# ArduinoSIDInterface.net
KiCad netlist of a schematic drawn in EAGLE
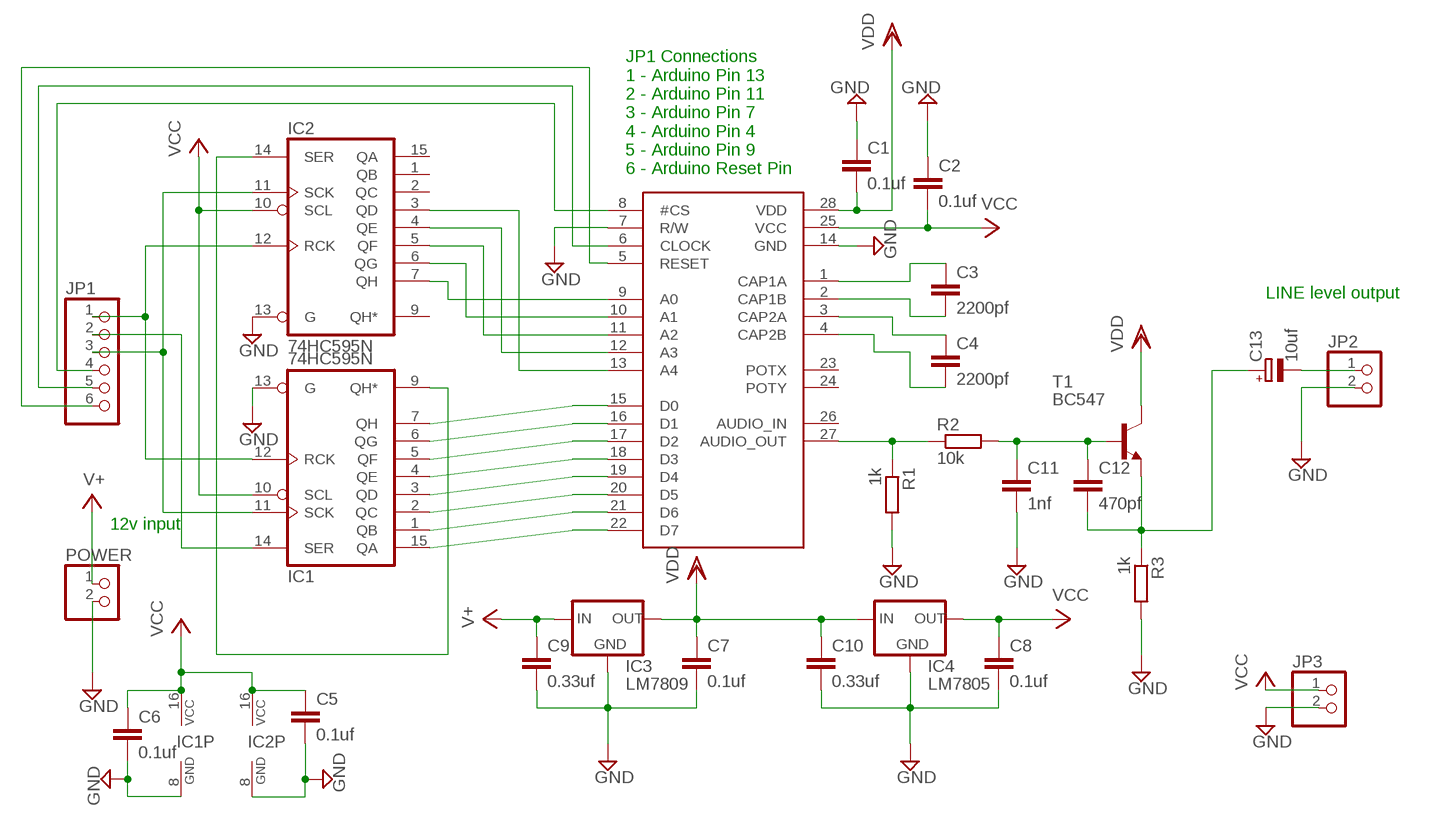
[diagram p0: schematic, sheet 1]

(export (version "E")
  (design (tool "Eeschema 10.0.6"))
  (components
    (comp (ref "C1")
      (value "0.1uf")
      (footprint "eagle-import:C050-035X075")
      (libsource (lib "eagle-import") (part "C-EU050-035X075"))
    )
    (comp (ref "C2")
      (value "0.1uf")
      (footprint "eagle-import:C050-030X075")
      (libsource (lib "eagle-import") (part "C-EU050-030X075"))
    )
    (comp (ref "C3")
      (value "2200pf")
      (footprint "eagle-import:C075-042X103")
      (libsource (lib "eagle-import") (part "C-EU075-042X103"))
    )
    (comp (ref "C4")
      (value "2200pf")
      (footprint "eagle-import:C075-042X103")
      (libsource (lib "eagle-import") (part "C-EU075-042X103"))
    )
    (comp (ref "C5")
      (value "0.1uf")
      (footprint "eagle-import:C050-030X075")
      (libsource (lib "eagle-import") (part "C-EU050-030X075"))
    )
    (comp (ref "C6")
      (value "0.1uf")
      (footprint "eagle-import:C050-030X075")
      (libsource (lib "eagle-import") (part "C-EU050-030X075"))
    )
    (comp (ref "C7")
      (value "0.1uf")
      (footprint "eagle-import:C10B4")
      (libsource (lib "eagle-import") (part "C10/4"))
    )
    (comp (ref "C8")
      (value "0.1uf")
      (footprint "eagle-import:C10B4")
      (libsource (lib "eagle-import") (part "C10/4"))
    )
    (comp (ref "C9")
      (value "0.33uf")
      (footprint "eagle-import:C15B5")
      (libsource (lib "eagle-import") (part "C15/5"))
    )
    (comp (ref "C10")
      (value "0.33uf")
      (footprint "eagle-import:C15B5")
      (libsource (lib "eagle-import") (part "C15/5"))
    )
    (comp (ref "C11")
      (value "1nf")
      (footprint "eagle-import:C050-030X075")
      (libsource (lib "eagle-import") (part "C-EU050-030X075"))
    )
    (comp (ref "C12")
      (value "470pf")
      (footprint "eagle-import:C050-030X075")
      (libsource (lib "eagle-import") (part "C-EU050-030X075"))
    )
    (comp (ref "C13")
      (value "10uf")
      (footprint "eagle-import:E2-5")
      (libsource (lib "eagle-import") (part "CPOL-EUE2-5"))
    )
    (comp (ref "IC1")
      (value "74HC595N")
      (footprint "eagle-import:DIL16")
      (libsource (lib "eagle-import") (part "74595NHC"))
    )
    (comp (ref "IC2")
      (value "74HC595N")
      (footprint "eagle-import:DIL16")
      (libsource (lib "eagle-import") (part "74595NHC"))
    )
    (comp (ref "IC3")
      (value "LM7809")
      (footprint "eagle-import:78XXS")
      (libsource (lib "eagle-import") (part "78XXS"))
    )
    (comp (ref "IC4")
      (value "LM7805")
      (footprint "eagle-import:78XXS")
      (libsource (lib "eagle-import") (part "78XXS"))
    )
    (comp (ref "JP1")
      (value "PINHD-1X6")
      (footprint "eagle-import:1X06")
      (libsource (lib "eagle-import") (part "PINHD-1X6"))
    )
    (comp (ref "JP2")
      (value "PINHD-1X2")
      (footprint "eagle-import:1X02")
      (libsource (lib "eagle-import") (part "PINHD-1X2"))
    )
    (comp (ref "JP3")
      (value "PINHD-1X2")
      (footprint "eagle-import:1X02")
      (libsource (lib "eagle-import") (part "PINHD-1X2"))
    )
    (comp (ref "POWER")
      (value "PINHD-1X2")
      (footprint "eagle-import:1X02")
      (libsource (lib "eagle-import") (part "PINHD-1X2"))
    )
    (comp (ref "R1")
      (value "1k")
      (footprint "eagle-import:0204_7")
      (libsource (lib "eagle-import") (part "R-EU_0204/7"))
    )
    (comp (ref "R2")
      (value "10k")
      (footprint "eagle-import:0204_7")
      (libsource (lib "eagle-import") (part "R-EU_0204/7"))
    )
    (comp (ref "R3")
      (value "1k")
      (footprint "eagle-import:0204_7")
      (libsource (lib "eagle-import") (part "R-EU_0204/7"))
    )
    (comp (ref "T1")
      (value "BC547")
      (footprint "eagle-import:TO92")
      (libsource (lib "eagle-import") (part "BC547"))
    )
    (comp (ref "U$1")
      (value "6581")
      (footprint "eagle-import:DIL28-6")
      (libsource (lib "eagle-import") (part "6581"))
    )
  )
  (nets
    (net (code "1") (name "/D0") (class "Default")
      (node (ref "IC1") (pin "7") (pinfunction "QH_7") (pintype "tri_state"))
      (node (ref "U$1") (pin "15") (pinfunction "D0_15") (pintype "bidirectional"))
    )
    (net (code "2") (name "/D1") (class "Default")
      (node (ref "IC1") (pin "6") (pinfunction "QG_6") (pintype "tri_state"))
      (node (ref "U$1") (pin "16") (pinfunction "D1_16") (pintype "bidirectional"))
    )
    (net (code "3") (name "/D2") (class "Default")
      (node (ref "IC1") (pin "5") (pinfunction "QF_5") (pintype "tri_state"))
      (node (ref "U$1") (pin "17") (pinfunction "D2_17") (pintype "bidirectional"))
    )
    (net (code "4") (name "/D3") (class "Default")
      (node (ref "IC1") (pin "4") (pinfunction "QE_4") (pintype "tri_state"))
      (node (ref "U$1") (pin "18") (pinfunction "D3_18") (pintype "bidirectional"))
    )
    (net (code "5") (name "/D4") (class "Default")
      (node (ref "IC1") (pin "3") (pinfunction "QD_3") (pintype "tri_state"))
      (node (ref "U$1") (pin "19") (pinfunction "D4_19") (pintype "bidirectional"))
    )
    (net (code "6") (name "/D5") (class "Default")
      (node (ref "IC1") (pin "2") (pinfunction "QC_2") (pintype "tri_state"))
      (node (ref "U$1") (pin "20") (pinfunction "D5_20") (pintype "bidirectional"))
    )
    (net (code "7") (name "/D6") (class "Default")
      (node (ref "IC1") (pin "1") (pinfunction "QB_1") (pintype "tri_state"))
      (node (ref "U$1") (pin "21") (pinfunction "D6_21") (pintype "bidirectional"))
    )
    (net (code "8") (name "/D7") (class "Default")
      (node (ref "IC1") (pin "15") (pinfunction "QA_15") (pintype "tri_state"))
      (node (ref "U$1") (pin "22") (pinfunction "D7_22") (pintype "bidirectional"))
    )
    (net (code "9") (name "GND") (class "Default")
      (node (ref "C1") (pin "1") (pinfunction "1_1") (pintype "passive"))
      (node (ref "C10") (pin "2") (pinfunction "2_2") (pintype "passive"))
      (node (ref "C11") (pin "2") (pinfunction "2_2") (pintype "passive"))
      (node (ref "C2") (pin "1") (pinfunction "1_1") (pintype "passive"))
      (node (ref "C5") (pin "2") (pinfunction "2_2") (pintype "passive"))
      (node (ref "C6") (pin "2") (pinfunction "2_2") (pintype "passive"))
      (node (ref "C7") (pin "2") (pinfunction "2_2") (pintype "passive"))
      (node (ref "C8") (pin "2") (pinfunction "2_2") (pintype "passive"))
      (node (ref "C9") (pin "2") (pinfunction "2_2") (pintype "passive"))
      (node (ref "IC1") (pin "13") (pinfunction "G_13") (pintype "input"))
      (node (ref "IC1") (pin "8") (pinfunction "GND_8") (pintype "power_in"))
      (node (ref "IC2") (pin "13") (pinfunction "G_13") (pintype "input"))
      (node (ref "IC2") (pin "8") (pinfunction "GND_8") (pintype "power_in"))
      (node (ref "IC3") (pin "GND") (pinfunction "GND_GND") (pintype "input"))
      (node (ref "IC4") (pin "GND") (pinfunction "GND_GND") (pintype "input"))
      (node (ref "JP2") (pin "2") (pinfunction "2_2") (pintype "passive"))
      (node (ref "JP3") (pin "2") (pinfunction "2_2") (pintype "passive"))
      (node (ref "POWER") (pin "2") (pinfunction "2_2") (pintype "passive"))
      (node (ref "R1") (pin "2") (pinfunction "2_2") (pintype "passive"))
      (node (ref "R3") (pin "2") (pinfunction "2_2") (pintype "passive"))
      (node (ref "U$1") (pin "14") (pinfunction "GND_14") (pintype "bidirectional"))
      (node (ref "U$1") (pin "7") (pinfunction "R/W_7") (pintype "bidirectional"))
    )
    (net (code "10") (name "Net-(C13-Pad-)") (class "Default")
      (node (ref "C13") (pin "-") (pinfunction "-_-") (pintype "passive"))
      (node (ref "JP2") (pin "1") (pinfunction "1_1") (pintype "passive"))
    )
    (net (code "11") (name "Net-(IC1A-QH*)") (class "Default")
      (node (ref "IC1") (pin "9") (pinfunction "QH*_9") (pintype "tri_state"))
      (node (ref "IC2") (pin "14") (pinfunction "SER_14") (pintype "input"))
    )
    (net (code "12") (name "Net-(IC1A-RCK)") (class "Default")
      (node (ref "IC1") (pin "12") (pinfunction "RCK_12") (pintype "input"))
      (node (ref "IC2") (pin "12") (pinfunction "RCK_12") (pintype "input"))
      (node (ref "JP1") (pin "1") (pinfunction "1_1") (pintype "passive"))
    )
    (net (code "13") (name "Net-(IC1A-SCK)") (class "Default")
      (node (ref "IC1") (pin "11") (pinfunction "SCK_11") (pintype "input"))
      (node (ref "IC2") (pin "11") (pinfunction "SCK_11") (pintype "input"))
      (node (ref "JP1") (pin "3") (pinfunction "3_3") (pintype "passive"))
    )
    (net (code "14") (name "Net-(IC1A-SER)") (class "Default")
      (node (ref "IC1") (pin "14") (pinfunction "SER_14") (pintype "input"))
      (node (ref "JP1") (pin "2") (pinfunction "2_2") (pintype "passive"))
    )
    (net (code "15") (name "Net-(IC2A-QD)") (class "Default")
      (node (ref "IC2") (pin "3") (pinfunction "QD_3") (pintype "tri_state"))
      (node (ref "U$1") (pin "13") (pinfunction "A4_13") (pintype "bidirectional"))
    )
    (net (code "16") (name "Net-(IC2A-QE)") (class "Default")
      (node (ref "IC2") (pin "4") (pinfunction "QE_4") (pintype "tri_state"))
      (node (ref "U$1") (pin "12") (pinfunction "A3_12") (pintype "bidirectional"))
    )
    (net (code "17") (name "Net-(IC2A-QF)") (class "Default")
      (node (ref "IC2") (pin "5") (pinfunction "QF_5") (pintype "tri_state"))
      (node (ref "U$1") (pin "11") (pinfunction "A2_11") (pintype "bidirectional"))
    )
    (net (code "18") (name "Net-(IC2A-QG)") (class "Default")
      (node (ref "IC2") (pin "6") (pinfunction "QG_6") (pintype "tri_state"))
      (node (ref "U$1") (pin "10") (pinfunction "A1_10") (pintype "bidirectional"))
    )
    (net (code "19") (name "Net-(IC2A-QH)") (class "Default")
      (node (ref "IC2") (pin "7") (pinfunction "QH_7") (pintype "tri_state"))
      (node (ref "U$1") (pin "9") (pinfunction "A0_9") (pintype "bidirectional"))
    )
    (net (code "20") (name "Net-(T1-B)") (class "Default")
      (node (ref "C11") (pin "1") (pinfunction "1_1") (pintype "passive"))
      (node (ref "C12") (pin "1") (pinfunction "1_1") (pintype "passive"))
      (node (ref "R2") (pin "2") (pinfunction "2_2") (pintype "passive"))
      (node (ref "T1") (pin "2") (pinfunction "B_2") (pintype "passive"))
    )
    (net (code "21") (name "Net-(T1-E)") (class "Default")
      (node (ref "C12") (pin "2") (pinfunction "2_2") (pintype "passive"))
      (node (ref "C13") (pin "+") (pinfunction "+_+") (pintype "passive"))
      (node (ref "R3") (pin "1") (pinfunction "1_1") (pintype "passive"))
      (node (ref "T1") (pin "1") (pinfunction "E_1") (pintype "passive"))
    )
    (net (code "22") (name "Net-(U$1-#CS)") (class "Default")
      (node (ref "JP1") (pin "4") (pinfunction "4_4") (pintype "passive"))
      (node (ref "U$1") (pin "8") (pinfunction "#CS_8") (pintype "bidirectional"))
    )
    (net (code "23") (name "Net-(U$1-AUDIO_OUT)") (class "Default")
      (node (ref "R1") (pin "1") (pinfunction "1_1") (pintype "passive"))
      (node (ref "R2") (pin "1") (pinfunction "1_1") (pintype "passive"))
      (node (ref "U$1") (pin "27") (pinfunction "AUDIO_OUT_27") (pintype "bidirectional"))
    )
    (net (code "24") (name "Net-(U$1-CAP1A)") (class "Default")
      (node (ref "C3") (pin "1") (pinfunction "1_1") (pintype "passive"))
      (node (ref "U$1") (pin "1") (pinfunction "CAP1A_1") (pintype "bidirectional"))
    )
    (net (code "25") (name "Net-(U$1-CAP1B)") (class "Default")
      (node (ref "C3") (pin "2") (pinfunction "2_2") (pintype "passive"))
      (node (ref "U$1") (pin "2") (pinfunction "CAP1B_2") (pintype "bidirectional"))
    )
    (net (code "26") (name "Net-(U$1-CAP2A)") (class "Default")
      (node (ref "C4") (pin "1") (pinfunction "1_1") (pintype "passive"))
      (node (ref "U$1") (pin "3") (pinfunction "CAP2A_3") (pintype "bidirectional"))
    )
    (net (code "27") (name "Net-(U$1-CAP2B)") (class "Default")
      (node (ref "C4") (pin "2") (pinfunction "2_2") (pintype "passive"))
      (node (ref "U$1") (pin "4") (pinfunction "CAP2B_4") (pintype "bidirectional"))
    )
    (net (code "28") (name "Net-(U$1-CLOCK)") (class "Default")
      (node (ref "JP1") (pin "5") (pinfunction "5_5") (pintype "passive"))
      (node (ref "U$1") (pin "6") (pinfunction "CLOCK_6") (pintype "bidirectional"))
    )
    (net (code "29") (name "Net-(U$1-RESET)") (class "Default")
      (node (ref "JP1") (pin "6") (pinfunction "6_6") (pintype "passive"))
      (node (ref "U$1") (pin "5") (pinfunction "RESET_5") (pintype "bidirectional"))
    )
    (net (code "30") (name "V+") (class "Default")
      (node (ref "C9") (pin "1") (pinfunction "1_1") (pintype "passive"))
      (node (ref "IC3") (pin "IN") (pinfunction "IN_IN") (pintype "input"))
      (node (ref "POWER") (pin "1") (pinfunction "1_1") (pintype "passive"))
    )
    (net (code "31") (name "VCC") (class "Default")
      (node (ref "C2") (pin "2") (pinfunction "2_2") (pintype "passive"))
      (node (ref "C5") (pin "1") (pinfunction "1_1") (pintype "passive"))
      (node (ref "C6") (pin "1") (pinfunction "1_1") (pintype "passive"))
      (node (ref "C8") (pin "1") (pinfunction "1_1") (pintype "passive"))
      (node (ref "IC1") (pin "10") (pinfunction "SCL_10") (pintype "input"))
      (node (ref "IC1") (pin "16") (pinfunction "VCC_16") (pintype "power_in"))
      (node (ref "IC2") (pin "10") (pinfunction "SCL_10") (pintype "input"))
      (node (ref "IC2") (pin "16") (pinfunction "VCC_16") (pintype "power_in"))
      (node (ref "IC4") (pin "OUT") (pinfunction "OUT_OUT") (pintype "passive"))
      (node (ref "JP3") (pin "1") (pinfunction "1_1") (pintype "passive"))
      (node (ref "U$1") (pin "25") (pinfunction "VCC_25") (pintype "bidirectional"))
    )
    (net (code "32") (name "VDD") (class "Default")
      (node (ref "C1") (pin "2") (pinfunction "2_2") (pintype "passive"))
      (node (ref "C10") (pin "1") (pinfunction "1_1") (pintype "passive"))
      (node (ref "C7") (pin "1") (pinfunction "1_1") (pintype "passive"))
      (node (ref "IC3") (pin "OUT") (pinfunction "OUT_OUT") (pintype "passive"))
      (node (ref "IC4") (pin "IN") (pinfunction "IN_IN") (pintype "input"))
      (node (ref "T1") (pin "3") (pinfunction "C_3") (pintype "passive"))
      (node (ref "U$1") (pin "28") (pinfunction "VDD_28") (pintype "bidirectional"))
    )
    (net (code "33") (name "unconnected-(IC2A-QA-Pad15)") (class "Default")
      (node (ref "IC2") (pin "15") (pinfunction "QA_15") (pintype "tri_state"))
    )
    (net (code "34") (name "unconnected-(IC2A-QB-Pad1)") (class "Default")
      (node (ref "IC2") (pin "1") (pinfunction "QB_1") (pintype "tri_state"))
    )
    (net (code "35") (name "unconnected-(IC2A-QC-Pad2)") (class "Default")
      (node (ref "IC2") (pin "2") (pinfunction "QC_2") (pintype "tri_state"))
    )
    (net (code "36") (name "unconnected-(IC2A-QH*-Pad9)") (class "Default")
      (node (ref "IC2") (pin "9") (pinfunction "QH*_9") (pintype "tri_state"))
    )
    (net (code "37") (name "unconnected-(U$1-AUDIO_IN-Pad26)") (class "Default")
      (node (ref "U$1") (pin "26") (pinfunction "AUDIO_IN_26") (pintype "bidirectional"))
    )
    (net (code "38") (name "unconnected-(U$1-POTX-Pad23)") (class "Default")
      (node (ref "U$1") (pin "23") (pinfunction "POTX_23") (pintype "bidirectional"))
    )
    (net (code "39") (name "unconnected-(U$1-POTY-Pad24)") (class "Default")
      (node (ref "U$1") (pin "24") (pinfunction "POTY_24") (pintype "bidirectional"))
    )
  )
)
